# UserInterface.net
KiCad netlist of a schematic drawn in Altium Designer
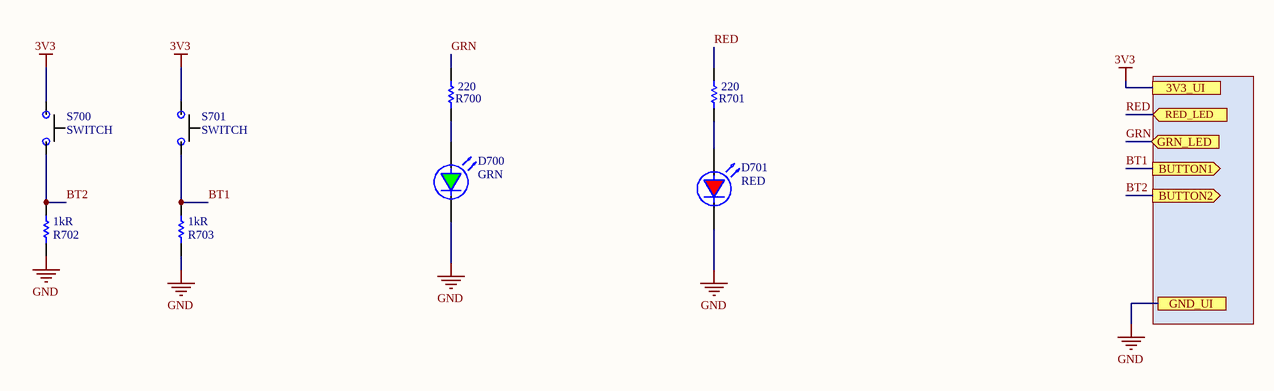
[diagram p0: UserInterface.SchDoc]

(export (version "E")
  (design (tool "Eeschema 10.0.6"))
  (components
    (comp (ref "D700")
      (value "GRN")
      (footprint "LED-5mm-VERDE")
      (description "LED GRN DIFF 5MM ROUND T/H")
      (fields
        (field (name "MANUFACTURER PART NUMBER") "LTL2R3KGD-EM")
        (field (name "MANUFACTURER") "Lite-On Inc.")
        (field (name "SOURCE") "mits.SchLib")
      )
      (libsource (lib "Mobit Brasil Ltda") (part "LED GRN DIFF 5MM ROUND T/H"))
    )
    (comp (ref "D701")
      (value "RED")
      (footprint "LED-5mm-VERMELHO")
      (description "LED RED DIFFUSED T-1 3/4 T/H")
      (fields
        (field (name "MANUFACTURER") "Lite-On Inc.")
        (field (name "VOLTAGE") "3V")
        (field (name "SOURCE") "mits.SchLib")
      )
      (libsource (lib "Mobit Brasil Ltda") (part "LED RED DIFF 5MM ROUND T/H"))
    )
    (comp (ref "R700")
      (value "RES 220R OHM 5% 1/8W 0805 SMD")
      (footprint "CR2012-0805")
      (description "RES SMD 220 OHM 5% 1/8W 0805")
      (fields
        (field (name "RESISTANCE (OHMS)") "220")
        (field (name "MANUFACTURER") "Panasonic Electronic Components")
        (field (name "TOLERANCE") "±5%")
        (field (name "SOURCE") "mits.SchLib")
      )
      (libsource (lib "Mobit Brasil Ltda") (part "Symbol"))
    )
    (comp (ref "R701")
      (value "RES 220R OHM 5% 1/8W 0805 SMD")
      (footprint "CR2012-0805")
      (description "RES SMD 220 OHM 5% 1/8W 0805")
      (fields
        (field (name "RESISTANCE (OHMS)") "220")
        (field (name "MANUFACTURER") "Panasonic Electronic Components")
        (field (name "TOLERANCE") "±5%")
        (field (name "SOURCE") "mits.SchLib")
      )
      (libsource (lib "Mobit Brasil Ltda") (part "Symbol"))
    )
    (comp (ref "R702")
      (value "RES 1K OHM 1% 1/8W 0805 SMD")
      (footprint "CR2012-0805")
      (description "RES SMD 1K OHM 1% 1/8W 0805")
      (fields
        (field (name "MANUFACTURER PART NUMBER") "RC0805FR-071KL")
        (field (name "RESISTANCE") "1kR")
        (field (name "TOLERANCE") "1%")
        (field (name "SOURCE") "mits.SchLib")
      )
      (libsource (lib "Mobit Brasil Ltda") (part "Symbol"))
    )
    (comp (ref "R703")
      (value "RES 1K OHM 1% 1/8W 0805 SMD")
      (footprint "CR2012-0805")
      (description "RES SMD 1K OHM 1% 1/8W 0805")
      (fields
        (field (name "MANUFACTURER PART NUMBER") "RC0805FR-071KL")
        (field (name "RESISTANCE") "1kR")
        (field (name "TOLERANCE") "1%")
        (field (name "SOURCE") "mits.SchLib")
      )
      (libsource (lib "Mobit Brasil Ltda") (part "Symbol"))
    )
    (comp (ref "S700")
      (value "SWITCH")
      (footprint "SWITCH_TACTILE_SMD_2PIN")
      (description "Switch Tactile N.O. SPST Rectangular Button J-Lead 0.05A 12VDC 2.55N SMD T/R")
      (fields
        (field (name "MANUFACTURER PART NUMBER") "TL3302BF260QJ")
        (field (name "MANUFACTURER") "E-Switch")
        (field (name "SOURCE") "mits.SchLib")
      )
      (libsource (lib "Mobit Brasil Ltda") (part "SWITCH TACTILE SPST-NO 0.05A 12V SMD"))
    )
    (comp (ref "S701")
      (value "SWITCH")
      (footprint "SWITCH_TACTILE_SMD_2PIN")
      (description "Switch Tactile N.O. SPST Rectangular Button J-Lead 0.05A 12VDC 2.55N SMD T/R")
      (fields
        (field (name "MANUFACTURER PART NUMBER") "TL3302BF260QJ")
        (field (name "MANUFACTURER") "E-Switch")
        (field (name "SOURCE") "mits.SchLib")
      )
      (libsource (lib "Mobit Brasil Ltda") (part "SWITCH TACTILE SPST-NO 0.05A 12V SMD"))
    )
  )
  (nets
    (net (code "1") (name "/BT1") (class "Default")
      (node (ref "R703") (pin "1") (pinfunction "1_1") (pintype "passive"))
      (node (ref "S701") (pin "1") (pinfunction "1_1") (pintype "passive"))
    )
    (net (code "2") (name "/BT2") (class "Default")
      (node (ref "R702") (pin "2") (pinfunction "2_2") (pintype "passive"))
      (node (ref "S700") (pin "1") (pinfunction "1_1") (pintype "passive"))
    )
    (net (code "3") (name "/GRN") (class "Default")
      (node (ref "R700") (pin "2") (pinfunction "2_2") (pintype "passive"))
    )
    (net (code "4") (name "/RED") (class "Default")
      (node (ref "R701") (pin "2") (pinfunction "2_2") (pintype "passive"))
    )
    (net (code "5") (name "3V3") (class "Default")
      (node (ref "S700") (pin "2") (pinfunction "2_2") (pintype "passive"))
      (node (ref "S701") (pin "2") (pinfunction "2_2") (pintype "passive"))
    )
    (net (code "6") (name "GND") (class "Default")
      (node (ref "D700") (pin "K") (pinfunction "K_K") (pintype "passive"))
      (node (ref "D701") (pin "K") (pinfunction "K_K") (pintype "passive"))
      (node (ref "R702") (pin "1") (pinfunction "1_1") (pintype "passive"))
      (node (ref "R703") (pin "2") (pinfunction "2_2") (pintype "passive"))
    )
    (net (code "7") (name "Net-(D700-PadA)") (class "Default")
      (node (ref "D700") (pin "A") (pinfunction "A_A") (pintype "passive"))
      (node (ref "R700") (pin "1") (pinfunction "1_1") (pintype "passive"))
    )
    (net (code "8") (name "Net-(D701-PadA)") (class "Default")
      (node (ref "D701") (pin "A") (pinfunction "A_A") (pintype "passive"))
      (node (ref "R701") (pin "1") (pinfunction "1_1") (pintype "passive"))
    )
  )
)
